# LEDboard.net
KiCad netlist of a schematic drawn in EAGLE
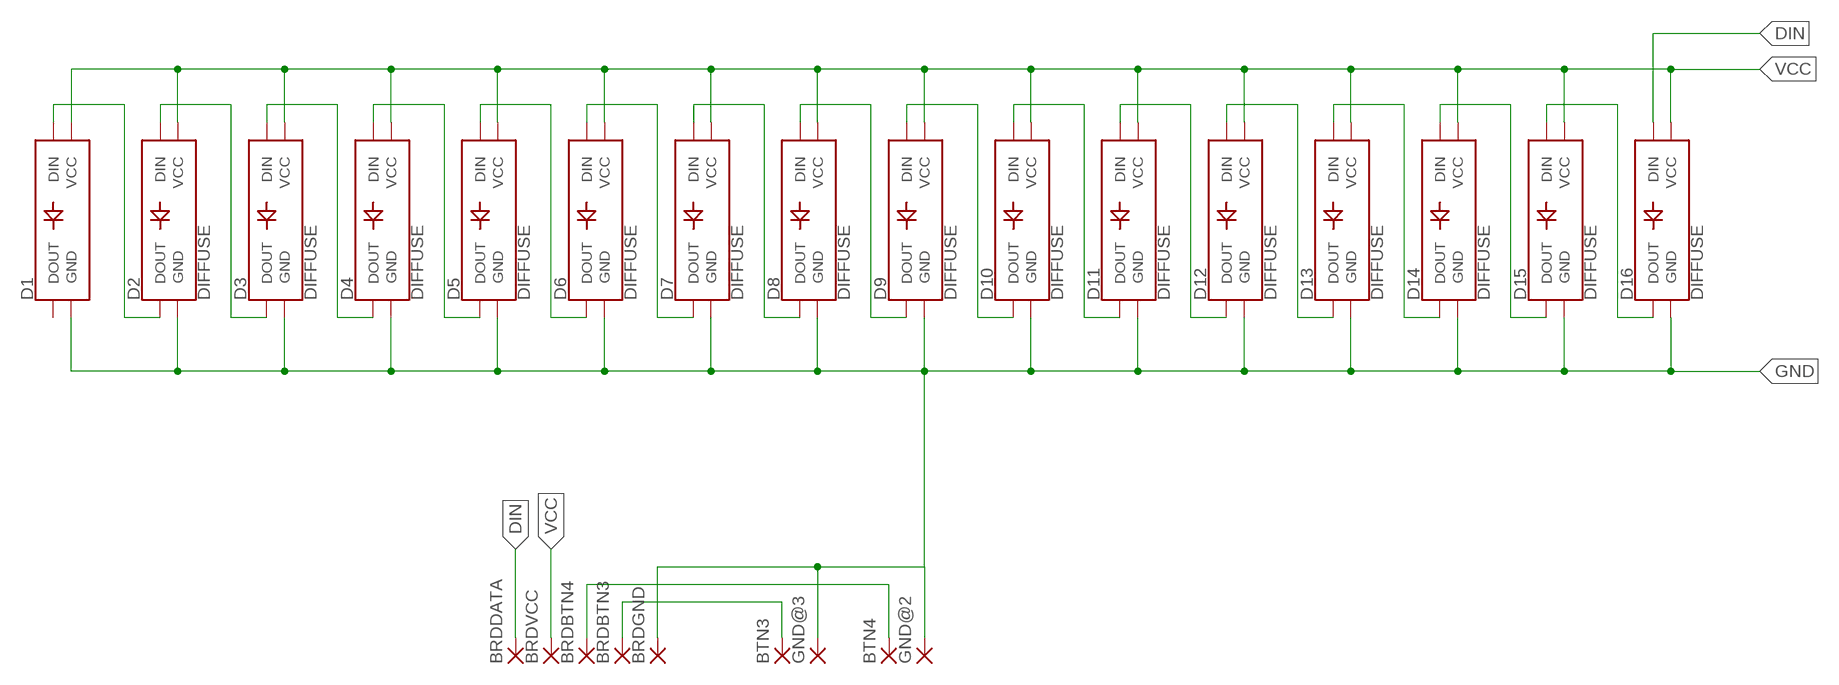
[diagram p0: schematic, sheet 1]

(export (version "E")
  (design (tool "Eeschema 10.0.6"))
  (components
    (comp (ref "BRDBTN3")
      (value "SMD5")
      (footprint "eagle-import:SMD2,54-5,08")
      (libsource (lib "eagle-import") (part "SMD5"))
    )
    (comp (ref "BRDBTN4")
      (value "SMD5")
      (footprint "eagle-import:SMD2,54-5,08")
      (libsource (lib "eagle-import") (part "SMD5"))
    )
    (comp (ref "BRDDATA")
      (value "SMD5")
      (footprint "eagle-import:SMD2,54-5,08")
      (libsource (lib "eagle-import") (part "SMD5"))
    )
    (comp (ref "BRDGND")
      (value "SMD5")
      (footprint "eagle-import:SMD2,54-5,08")
      (libsource (lib "eagle-import") (part "SMD5"))
    )
    (comp (ref "BRDVCC")
      (value "SMD5")
      (footprint "eagle-import:SMD2,54-5,08")
      (libsource (lib "eagle-import") (part "SMD5"))
    )
    (comp (ref "BTN3")
      (value "SMD5")
      (footprint "eagle-import:SMD2,54-5,08")
      (libsource (lib "eagle-import") (part "SMD5"))
    )
    (comp (ref "BTN4")
      (value "SMD5")
      (footprint "eagle-import:SMD2,54-5,08")
      (libsource (lib "eagle-import") (part "SMD5"))
    )
    (comp (ref "D1")
      (value "WS2812B_THT_ROUNDDIFFUSE")
      (footprint "eagle-import:WS2812B_THT_ROUND")
      (libsource (lib "eagle-import") (part "WS2812B_THT_ROUNDDIFFUSE"))
    )
    (comp (ref "D2")
      (value "DIFFUSE")
      (footprint "eagle-import:WS2812B_THT_ROUND")
      (libsource (lib "eagle-import") (part "WS2812B_THT_ROUNDDIFFUSE"))
    )
    (comp (ref "D3")
      (value "DIFFUSE")
      (footprint "eagle-import:WS2812B_THT_ROUND")
      (libsource (lib "eagle-import") (part "WS2812B_THT_ROUNDDIFFUSE"))
    )
    (comp (ref "D4")
      (value "DIFFUSE")
      (footprint "eagle-import:WS2812B_THT_ROUND")
      (libsource (lib "eagle-import") (part "WS2812B_THT_ROUNDDIFFUSE"))
    )
    (comp (ref "D5")
      (value "DIFFUSE")
      (footprint "eagle-import:WS2812B_THT_ROUND")
      (libsource (lib "eagle-import") (part "WS2812B_THT_ROUNDDIFFUSE"))
    )
    (comp (ref "D6")
      (value "DIFFUSE")
      (footprint "eagle-import:WS2812B_THT_ROUND")
      (libsource (lib "eagle-import") (part "WS2812B_THT_ROUNDDIFFUSE"))
    )
    (comp (ref "D7")
      (value "DIFFUSE")
      (footprint "eagle-import:WS2812B_THT_ROUND")
      (libsource (lib "eagle-import") (part "WS2812B_THT_ROUNDDIFFUSE"))
    )
    (comp (ref "D8")
      (value "DIFFUSE")
      (footprint "eagle-import:WS2812B_THT_ROUND")
      (libsource (lib "eagle-import") (part "WS2812B_THT_ROUNDDIFFUSE"))
    )
    (comp (ref "D9")
      (value "DIFFUSE")
      (footprint "eagle-import:WS2812B_THT_ROUND")
      (libsource (lib "eagle-import") (part "WS2812B_THT_ROUNDDIFFUSE"))
    )
    (comp (ref "D10")
      (value "DIFFUSE")
      (footprint "eagle-import:WS2812B_THT_ROUND")
      (libsource (lib "eagle-import") (part "WS2812B_THT_ROUNDDIFFUSE"))
    )
    (comp (ref "D11")
      (value "DIFFUSE")
      (footprint "eagle-import:WS2812B_THT_ROUND")
      (libsource (lib "eagle-import") (part "WS2812B_THT_ROUNDDIFFUSE"))
    )
    (comp (ref "D12")
      (value "DIFFUSE")
      (footprint "eagle-import:WS2812B_THT_ROUND")
      (libsource (lib "eagle-import") (part "WS2812B_THT_ROUNDDIFFUSE"))
    )
    (comp (ref "D13")
      (value "DIFFUSE")
      (footprint "eagle-import:WS2812B_THT_ROUND")
      (libsource (lib "eagle-import") (part "WS2812B_THT_ROUNDDIFFUSE"))
    )
    (comp (ref "D14")
      (value "DIFFUSE")
      (footprint "eagle-import:WS2812B_THT_ROUND")
      (libsource (lib "eagle-import") (part "WS2812B_THT_ROUNDDIFFUSE"))
    )
    (comp (ref "D15")
      (value "DIFFUSE")
      (footprint "eagle-import:WS2812B_THT_ROUND")
      (libsource (lib "eagle-import") (part "WS2812B_THT_ROUNDDIFFUSE"))
    )
    (comp (ref "D16")
      (value "DIFFUSE")
      (footprint "eagle-import:WS2812B_THT_ROUND")
      (libsource (lib "eagle-import") (part "WS2812B_THT_ROUNDDIFFUSE"))
    )
    (comp (ref "GND@2")
      (value "SMD5")
      (footprint "eagle-import:SMD2,54-5,08")
      (libsource (lib "eagle-import") (part "SMD5"))
    )
    (comp (ref "GND@3")
      (value "SMD5")
      (footprint "eagle-import:SMD2,54-5,08")
      (libsource (lib "eagle-import") (part "SMD5"))
    )
  )
  (nets
    (net (code "1") (name "DIN") (class "Default")
      (node (ref "BRDDATA") (pin "1") (pinfunction "P_1") (pintype "passive"))
      (node (ref "D16") (pin "1") (pinfunction "DIN_1") (pintype "input"))
    )
    (net (code "2") (name "GND") (class "Default")
      (node (ref "BRDGND") (pin "1") (pinfunction "P_1") (pintype "passive"))
      (node (ref "D1") (pin "3") (pinfunction "GND_3") (pintype "output"))
      (node (ref "D10") (pin "3") (pinfunction "GND_3") (pintype "output"))
      (node (ref "D11") (pin "3") (pinfunction "GND_3") (pintype "output"))
      (node (ref "D12") (pin "3") (pinfunction "GND_3") (pintype "output"))
      (node (ref "D13") (pin "3") (pinfunction "GND_3") (pintype "output"))
      (node (ref "D14") (pin "3") (pinfunction "GND_3") (pintype "output"))
      (node (ref "D15") (pin "3") (pinfunction "GND_3") (pintype "output"))
      (node (ref "D16") (pin "3") (pinfunction "GND_3") (pintype "output"))
      (node (ref "D2") (pin "3") (pinfunction "GND_3") (pintype "output"))
      (node (ref "D3") (pin "3") (pinfunction "GND_3") (pintype "output"))
      (node (ref "D4") (pin "3") (pinfunction "GND_3") (pintype "output"))
      (node (ref "D5") (pin "3") (pinfunction "GND_3") (pintype "output"))
      (node (ref "D6") (pin "3") (pinfunction "GND_3") (pintype "output"))
      (node (ref "D7") (pin "3") (pinfunction "GND_3") (pintype "output"))
      (node (ref "D8") (pin "3") (pinfunction "GND_3") (pintype "output"))
      (node (ref "D9") (pin "3") (pinfunction "GND_3") (pintype "output"))
      (node (ref "GND@2") (pin "1") (pinfunction "P_1") (pintype "passive"))
      (node (ref "GND@3") (pin "1") (pinfunction "P_1") (pintype "passive"))
    )
    (net (code "3") (name "Net-(BRDBTN3-P)") (class "Default")
      (node (ref "BRDBTN3") (pin "1") (pinfunction "P_1") (pintype "passive"))
      (node (ref "BTN3") (pin "1") (pinfunction "P_1") (pintype "passive"))
    )
    (net (code "4") (name "Net-(BRDBTN4-P)") (class "Default")
      (node (ref "BRDBTN4") (pin "1") (pinfunction "P_1") (pintype "passive"))
      (node (ref "BTN4") (pin "1") (pinfunction "P_1") (pintype "passive"))
    )
    (net (code "5") (name "Net-(D1-DIN)") (class "Default")
      (node (ref "D1") (pin "1") (pinfunction "DIN_1") (pintype "input"))
      (node (ref "D2") (pin "4") (pinfunction "DOUT_4") (pintype "output"))
    )
    (net (code "6") (name "Net-(D2-DIN)") (class "Default")
      (node (ref "D2") (pin "1") (pinfunction "DIN_1") (pintype "input"))
      (node (ref "D3") (pin "4") (pinfunction "DOUT_4") (pintype "output"))
    )
    (net (code "7") (name "Net-(D3-DIN)") (class "Default")
      (node (ref "D3") (pin "1") (pinfunction "DIN_1") (pintype "input"))
      (node (ref "D4") (pin "4") (pinfunction "DOUT_4") (pintype "output"))
    )
    (net (code "8") (name "Net-(D4-DIN)") (class "Default")
      (node (ref "D4") (pin "1") (pinfunction "DIN_1") (pintype "input"))
      (node (ref "D5") (pin "4") (pinfunction "DOUT_4") (pintype "output"))
    )
    (net (code "9") (name "Net-(D5-DIN)") (class "Default")
      (node (ref "D5") (pin "1") (pinfunction "DIN_1") (pintype "input"))
      (node (ref "D6") (pin "4") (pinfunction "DOUT_4") (pintype "output"))
    )
    (net (code "10") (name "Net-(D6-DIN)") (class "Default")
      (node (ref "D6") (pin "1") (pinfunction "DIN_1") (pintype "input"))
      (node (ref "D7") (pin "4") (pinfunction "DOUT_4") (pintype "output"))
    )
    (net (code "11") (name "Net-(D7-DIN)") (class "Default")
      (node (ref "D7") (pin "1") (pinfunction "DIN_1") (pintype "input"))
      (node (ref "D8") (pin "4") (pinfunction "DOUT_4") (pintype "output"))
    )
    (net (code "12") (name "Net-(D8-DIN)") (class "Default")
      (node (ref "D8") (pin "1") (pinfunction "DIN_1") (pintype "input"))
      (node (ref "D9") (pin "4") (pinfunction "DOUT_4") (pintype "output"))
    )
    (net (code "13") (name "Net-(D10-DIN)") (class "Default")
      (node (ref "D10") (pin "1") (pinfunction "DIN_1") (pintype "input"))
      (node (ref "D11") (pin "4") (pinfunction "DOUT_4") (pintype "output"))
    )
    (net (code "14") (name "Net-(D10-DOUT)") (class "Default")
      (node (ref "D10") (pin "4") (pinfunction "DOUT_4") (pintype "output"))
      (node (ref "D9") (pin "1") (pinfunction "DIN_1") (pintype "input"))
    )
    (net (code "15") (name "Net-(D11-DIN)") (class "Default")
      (node (ref "D11") (pin "1") (pinfunction "DIN_1") (pintype "input"))
      (node (ref "D12") (pin "4") (pinfunction "DOUT_4") (pintype "output"))
    )
    (net (code "16") (name "Net-(D12-DIN)") (class "Default")
      (node (ref "D12") (pin "1") (pinfunction "DIN_1") (pintype "input"))
      (node (ref "D13") (pin "4") (pinfunction "DOUT_4") (pintype "output"))
    )
    (net (code "17") (name "Net-(D13-DIN)") (class "Default")
      (node (ref "D13") (pin "1") (pinfunction "DIN_1") (pintype "input"))
      (node (ref "D14") (pin "4") (pinfunction "DOUT_4") (pintype "output"))
    )
    (net (code "18") (name "Net-(D14-DIN)") (class "Default")
      (node (ref "D14") (pin "1") (pinfunction "DIN_1") (pintype "input"))
      (node (ref "D15") (pin "4") (pinfunction "DOUT_4") (pintype "output"))
    )
    (net (code "19") (name "Net-(D15-DIN)") (class "Default")
      (node (ref "D15") (pin "1") (pinfunction "DIN_1") (pintype "input"))
      (node (ref "D16") (pin "4") (pinfunction "DOUT_4") (pintype "output"))
    )
    (net (code "20") (name "VCC") (class "Default")
      (node (ref "BRDVCC") (pin "1") (pinfunction "P_1") (pintype "passive"))
      (node (ref "D1") (pin "2") (pinfunction "VCC_2") (pintype "input"))
      (node (ref "D10") (pin "2") (pinfunction "VCC_2") (pintype "input"))
      (node (ref "D11") (pin "2") (pinfunction "VCC_2") (pintype "input"))
      (node (ref "D12") (pin "2") (pinfunction "VCC_2") (pintype "input"))
      (node (ref "D13") (pin "2") (pinfunction "VCC_2") (pintype "input"))
      (node (ref "D14") (pin "2") (pinfunction "VCC_2") (pintype "input"))
      (node (ref "D15") (pin "2") (pinfunction "VCC_2") (pintype "input"))
      (node (ref "D16") (pin "2") (pinfunction "VCC_2") (pintype "input"))
      (node (ref "D2") (pin "2") (pinfunction "VCC_2") (pintype "input"))
      (node (ref "D3") (pin "2") (pinfunction "VCC_2") (pintype "input"))
      (node (ref "D4") (pin "2") (pinfunction "VCC_2") (pintype "input"))
      (node (ref "D5") (pin "2") (pinfunction "VCC_2") (pintype "input"))
      (node (ref "D6") (pin "2") (pinfunction "VCC_2") (pintype "input"))
      (node (ref "D7") (pin "2") (pinfunction "VCC_2") (pintype "input"))
      (node (ref "D8") (pin "2") (pinfunction "VCC_2") (pintype "input"))
      (node (ref "D9") (pin "2") (pinfunction "VCC_2") (pintype "input"))
    )
    (net (code "21") (name "unconnected-(D1-DOUT-Pad4)") (class "Default")
      (node (ref "D1") (pin "4") (pinfunction "DOUT_4") (pintype "output"))
    )
  )
)
